# CCM_0020_transmitter.net
KiCad netlist of a schematic drawn in EAGLE
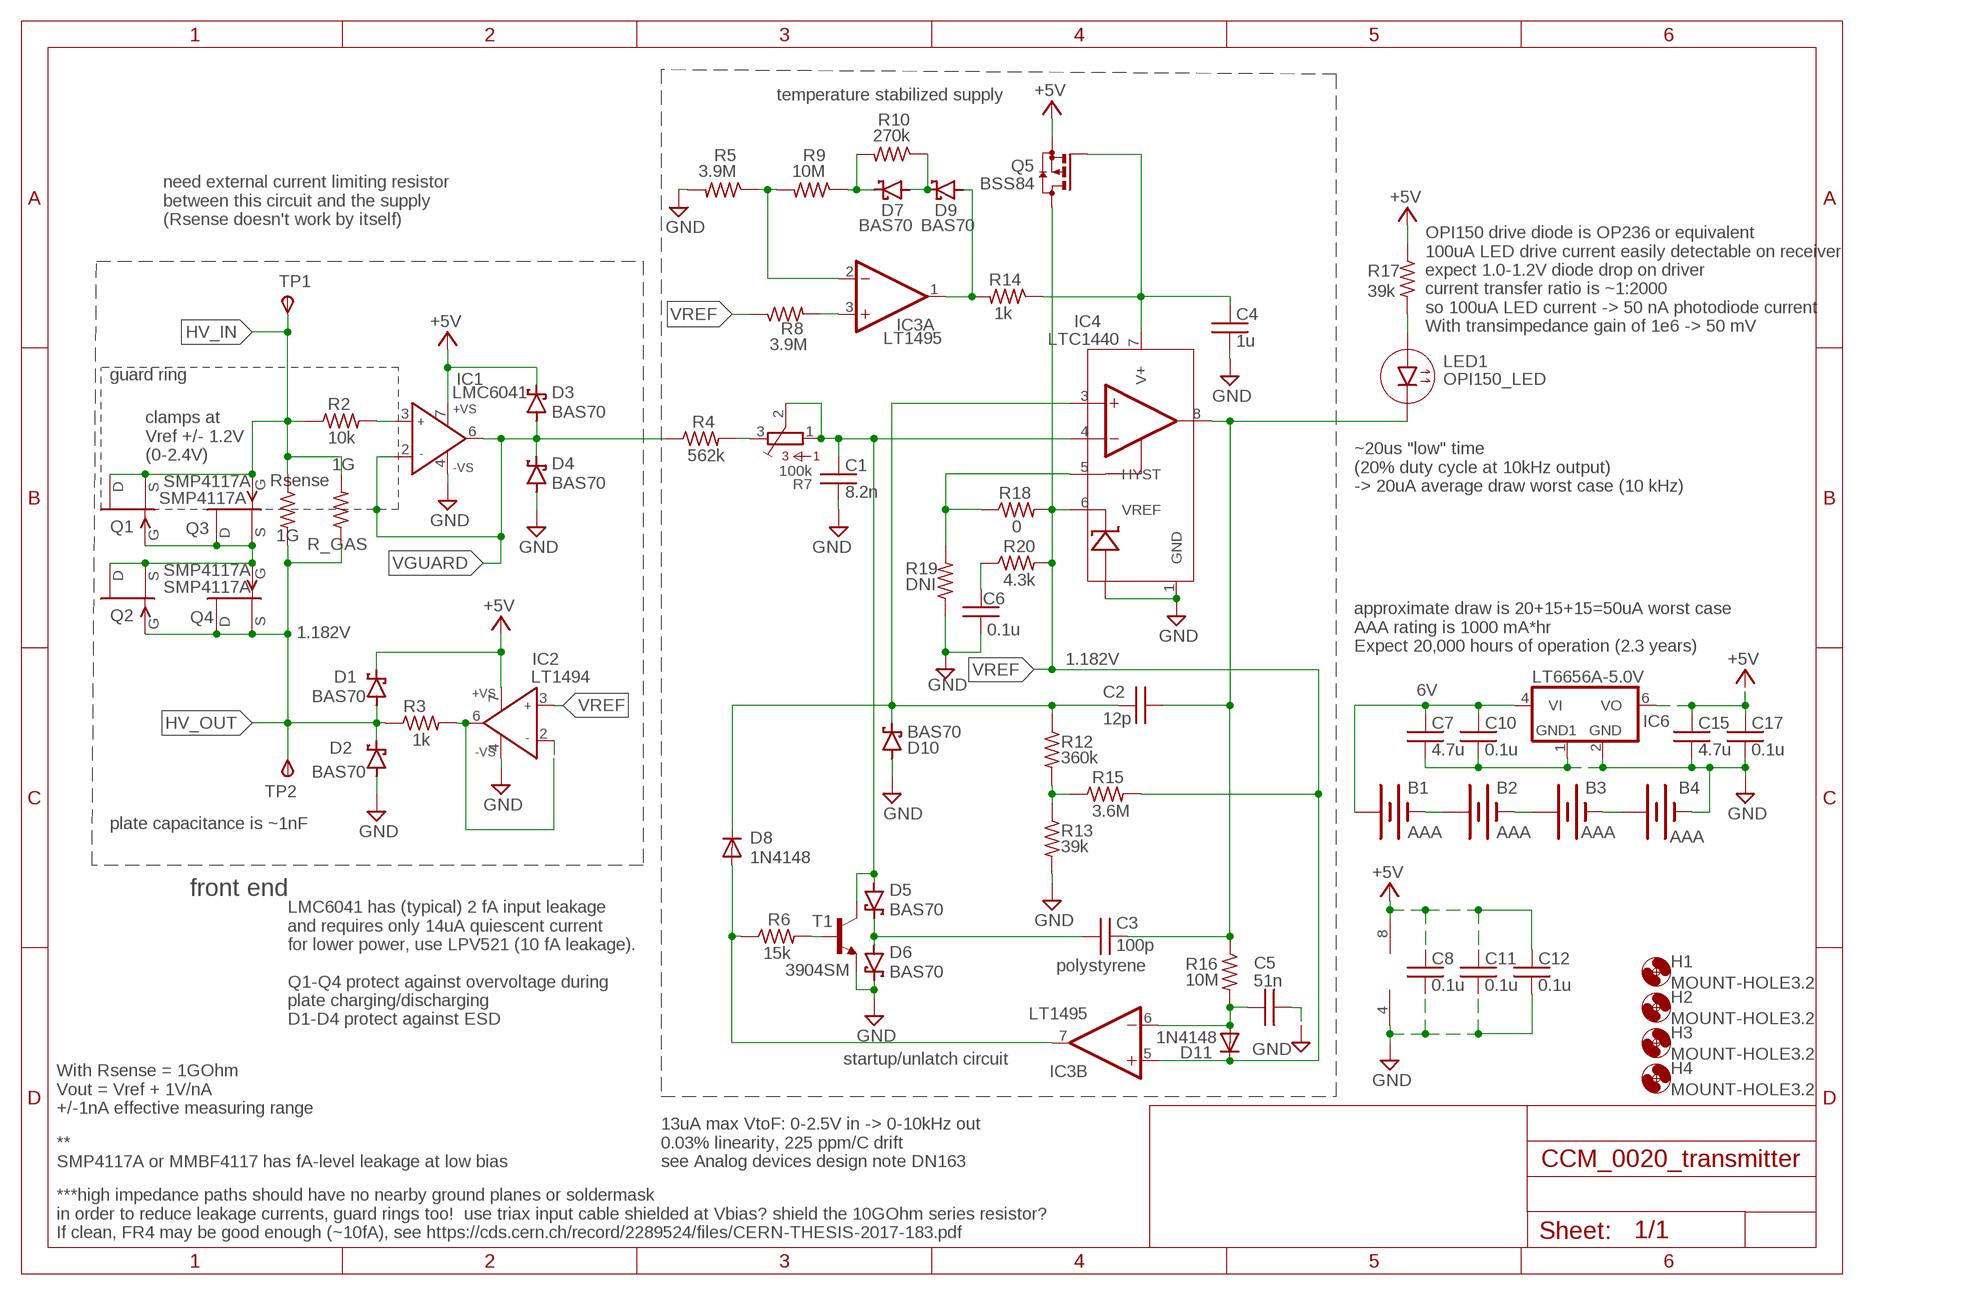
[diagram p0: schematic, sheet 1]

(export (version "E")
  (design (tool "Eeschema 10.0.6"))
  (components
    (comp (ref "B1")
      (value "AAA")
      (footprint "eagle-import:AAA_SM")
      (libsource (lib "eagle-import") (part "AAA"))
    )
    (comp (ref "B2")
      (value "AAA")
      (footprint "eagle-import:AAA_SM")
      (libsource (lib "eagle-import") (part "AAA"))
    )
    (comp (ref "B3")
      (value "AAA")
      (footprint "eagle-import:AAA_SM")
      (libsource (lib "eagle-import") (part "AAA"))
    )
    (comp (ref "B4")
      (value "AAA")
      (footprint "eagle-import:AAA_SM")
      (libsource (lib "eagle-import") (part "AAA"))
    )
    (comp (ref "C1")
      (value "8.2n")
      (footprint "eagle-import:0603")
      (libsource (lib "eagle-import") (part "C0603"))
    )
    (comp (ref "C2")
      (value "12p")
      (footprint "eagle-import:0603")
      (libsource (lib "eagle-import") (part "C0603"))
    )
    (comp (ref "C3")
      (value "100p")
      (footprint "eagle-import:0603")
      (libsource (lib "eagle-import") (part "C0603"))
    )
    (comp (ref "C4")
      (value "1u")
      (footprint "eagle-import:0603")
      (libsource (lib "eagle-import") (part "C0603"))
    )
    (comp (ref "C5")
      (value "51n")
      (footprint "eagle-import:0603")
      (libsource (lib "eagle-import") (part "C0603"))
    )
    (comp (ref "C6")
      (value "0.1u")
      (footprint "eagle-import:0603")
      (libsource (lib "eagle-import") (part "C0603"))
    )
    (comp (ref "C7")
      (value "4.7u")
      (footprint "eagle-import:0603")
      (libsource (lib "eagle-import") (part "C0603"))
    )
    (comp (ref "C8")
      (value "0.1u")
      (footprint "eagle-import:0603")
      (libsource (lib "eagle-import") (part "C0603"))
    )
    (comp (ref "C10")
      (value "0.1u")
      (footprint "eagle-import:0603")
      (libsource (lib "eagle-import") (part "C0603"))
    )
    (comp (ref "C11")
      (value "0.1u")
      (footprint "eagle-import:0603")
      (libsource (lib "eagle-import") (part "C0603"))
    )
    (comp (ref "C12")
      (value "0.1u")
      (footprint "eagle-import:0603")
      (libsource (lib "eagle-import") (part "C0603"))
    )
    (comp (ref "C15")
      (value "4.7u")
      (footprint "eagle-import:0603")
      (libsource (lib "eagle-import") (part "C0603"))
    )
    (comp (ref "C17")
      (value "0.1u")
      (footprint "eagle-import:0603")
      (libsource (lib "eagle-import") (part "C0603"))
    )
    (comp (ref "D1")
      (value "BAS70")
      (footprint "eagle-import:SOT23")
      (libsource (lib "eagle-import") (part "BAS70"))
    )
    (comp (ref "D2")
      (value "BAS70")
      (footprint "eagle-import:SOT23")
      (libsource (lib "eagle-import") (part "BAS70"))
    )
    (comp (ref "D3")
      (value "BAS70")
      (footprint "eagle-import:SOT23")
      (libsource (lib "eagle-import") (part "BAS70"))
    )
    (comp (ref "D4")
      (value "BAS70")
      (footprint "eagle-import:SOT23")
      (libsource (lib "eagle-import") (part "BAS70"))
    )
    (comp (ref "D5")
      (value "BAS70")
      (footprint "eagle-import:SOT23")
      (libsource (lib "eagle-import") (part "BAS70"))
    )
    (comp (ref "D6")
      (value "BAS70")
      (footprint "eagle-import:SOT23")
      (libsource (lib "eagle-import") (part "BAS70"))
    )
    (comp (ref "D7")
      (value "BAS70")
      (footprint "eagle-import:SOT23")
      (libsource (lib "eagle-import") (part "BAS70"))
    )
    (comp (ref "D8")
      (value "1N4148")
      (footprint "eagle-import:SOD323_ST")
      (libsource (lib "eagle-import") (part "1N4148"))
    )
    (comp (ref "D9")
      (value "BAS70")
      (footprint "eagle-import:SOT23")
      (libsource (lib "eagle-import") (part "BAS70"))
    )
    (comp (ref "D10")
      (value "BAS70")
      (footprint "eagle-import:SOT23")
      (libsource (lib "eagle-import") (part "BAS70"))
    )
    (comp (ref "D11")
      (value "1N4148")
      (footprint "eagle-import:SOD323_ST")
      (libsource (lib "eagle-import") (part "1N4148"))
    )
    (comp (ref "H1")
      (value "MOUNT-HOLE3.2")
      (footprint "eagle-import:3,2")
      (libsource (lib "eagle-import") (part "MOUNT-HOLE3.2"))
    )
    (comp (ref "H2")
      (value "MOUNT-HOLE3.2")
      (footprint "eagle-import:3,2")
      (libsource (lib "eagle-import") (part "MOUNT-HOLE3.2"))
    )
    (comp (ref "H3")
      (value "MOUNT-HOLE3.2")
      (footprint "eagle-import:3,2")
      (libsource (lib "eagle-import") (part "MOUNT-HOLE3.2"))
    )
    (comp (ref "H4")
      (value "MOUNT-HOLE3.2")
      (footprint "eagle-import:3,2")
      (libsource (lib "eagle-import") (part "MOUNT-HOLE3.2"))
    )
    (comp (ref "IC1")
      (value "LMC6041")
      (footprint "eagle-import:SO08")
      (libsource (lib "eagle-import") (part "AD825_A"))
    )
    (comp (ref "IC2")
      (value "LT1494")
      (footprint "eagle-import:SO08")
      (libsource (lib "eagle-import") (part "AD825_A"))
    )
    (comp (ref "IC3")
      (value "LT1495")
      (footprint "eagle-import:SO08")
      (libsource (lib "eagle-import") (part "LM393D"))
    )
    (comp (ref "IC4")
      (value "LTC1440")
      (footprint "eagle-import:SO8")
      (libsource (lib "eagle-import") (part "LTC1440"))
    )
    (comp (ref "IC6")
      (value "LT6656A-5.0V")
      (footprint "eagle-import:SOT23-6")
      (libsource (lib "eagle-import") (part "LT6656"))
    )
    (comp (ref "LED1")
      (value "OPI150_LED")
      (footprint "eagle-import:OPI150_LED")
      (libsource (lib "eagle-import") (part "OPI150_LED"))
    )
    (comp (ref "Q1")
      (value "SMP4117A")
      (footprint "eagle-import:SOT23")
      (libsource (lib "eagle-import") (part "?548SST4"))
    )
    (comp (ref "Q2")
      (value "SMP4117A")
      (footprint "eagle-import:SOT23")
      (libsource (lib "eagle-import") (part "?548SST4"))
    )
    (comp (ref "Q3")
      (value "SMP4117A")
      (footprint "eagle-import:SOT23")
      (libsource (lib "eagle-import") (part "?548SST4"))
    )
    (comp (ref "Q4")
      (value "SMP4117A")
      (footprint "eagle-import:SOT23")
      (libsource (lib "eagle-import") (part "?548SST4"))
    )
    (comp (ref "Q5")
      (value "BSS84")
      (footprint "eagle-import:SOT23")
      (libsource (lib "eagle-import") (part "BSS84"))
    )
    (comp (ref "R1")
      (value "1G")
      (footprint "eagle-import:2512")
      (libsource (lib "eagle-import") (part "RESISTOR2512"))
    )
    (comp (ref "R2")
      (value "10k")
      (footprint "eagle-import:0603")
      (libsource (lib "eagle-import") (part "R0603"))
    )
    (comp (ref "R3")
      (value "1k")
      (footprint "eagle-import:0603")
      (libsource (lib "eagle-import") (part "R0603"))
    )
    (comp (ref "R4")
      (value "562k")
      (footprint "eagle-import:0603")
      (libsource (lib "eagle-import") (part "R0603"))
    )
    (comp (ref "R5")
      (value "3.9M")
      (footprint "eagle-import:0603")
      (libsource (lib "eagle-import") (part "R0603"))
    )
    (comp (ref "R6")
      (value "15k")
      (footprint "eagle-import:0603")
      (libsource (lib "eagle-import") (part "R0603"))
    )
    (comp (ref "R7")
      (value "100k")
      (footprint "eagle-import:3386C")
      (libsource (lib "eagle-import") (part "3386-C"))
    )
    (comp (ref "R8")
      (value "3.9M")
      (footprint "eagle-import:0603")
      (libsource (lib "eagle-import") (part "R0603"))
    )
    (comp (ref "R9")
      (value "10M")
      (footprint "eagle-import:0603")
      (libsource (lib "eagle-import") (part "R0603"))
    )
    (comp (ref "R10")
      (value "270k")
      (footprint "eagle-import:0603")
      (libsource (lib "eagle-import") (part "R0603"))
    )
    (comp (ref "R12")
      (value "360k")
      (footprint "eagle-import:0603")
      (libsource (lib "eagle-import") (part "R0603"))
    )
    (comp (ref "R13")
      (value "39k")
      (footprint "eagle-import:0603")
      (libsource (lib "eagle-import") (part "R0603"))
    )
    (comp (ref "R14")
      (value "1k")
      (footprint "eagle-import:0603")
      (libsource (lib "eagle-import") (part "R0603"))
    )
    (comp (ref "R15")
      (value "3.6M")
      (footprint "eagle-import:0603")
      (libsource (lib "eagle-import") (part "R0603"))
    )
    (comp (ref "R16")
      (value "10M")
      (footprint "eagle-import:0603")
      (libsource (lib "eagle-import") (part "R0603"))
    )
    (comp (ref "R17")
      (value "39k")
      (footprint "eagle-import:0603")
      (libsource (lib "eagle-import") (part "R0603"))
    )
    (comp (ref "R18")
      (value "0")
      (footprint "eagle-import:0603")
      (libsource (lib "eagle-import") (part "R0603"))
    )
    (comp (ref "R19")
      (value "DNI")
      (footprint "eagle-import:0603")
      (libsource (lib "eagle-import") (part "R0603"))
    )
    (comp (ref "R20")
      (value "4.3k")
      (footprint "eagle-import:0603")
      (libsource (lib "eagle-import") (part "R0603"))
    )
    (comp (ref "R_GAS")
      (value "1G")
      (footprint "eagle-import:0309_10")
      (libsource (lib "eagle-import") (part "R-US_0309/10"))
    )
    (comp (ref "T1")
      (value "3904SM")
      (footprint "eagle-import:SOT23")
      (libsource (lib "eagle-import") (part "3904SM"))
    )
    (comp (ref "TP1")
      (value "TPSPAD1-17")
      (footprint "eagle-import:P1-17")
      (libsource (lib "eagle-import") (part "TPSPAD1-17"))
    )
    (comp (ref "TP2")
      (value "TPSPAD1-17")
      (footprint "eagle-import:P1-17")
      (libsource (lib "eagle-import") (part "TPSPAD1-17"))
    )
  )
  (nets
    (net (code "1") (name "+5V") (class "Default")
      (node (ref "C11") (pin "1") (pinfunction "1_1") (pintype "passive"))
      (node (ref "C12") (pin "1") (pinfunction "1_1") (pintype "passive"))
      (node (ref "C15") (pin "1") (pinfunction "1_1") (pintype "passive"))
      (node (ref "C17") (pin "1") (pinfunction "1_1") (pintype "passive"))
      (node (ref "C8") (pin "1") (pinfunction "1_1") (pintype "passive"))
      (node (ref "D1") (pin "3") (pinfunction "C_3") (pintype "passive"))
      (node (ref "D3") (pin "3") (pinfunction "C_3") (pintype "passive"))
      (node (ref "IC1") (pin "7") (pinfunction "+VS_7") (pintype "input"))
      (node (ref "IC2") (pin "7") (pinfunction "+VS_7") (pintype "input"))
      (node (ref "IC3") (pin "8") (pinfunction "V+_8") (pintype "power_in"))
      (node (ref "IC6") (pin "6") (pinfunction "VO_6") (pintype "passive"))
      (node (ref "Q5") (pin "2") (pinfunction "S_2") (pintype "passive"))
      (node (ref "R17") (pin "1") (pinfunction "1_1") (pintype "passive"))
    )
    (net (code "2") (name "GND") (class "Default")
      (node (ref "B4") (pin "-") (pinfunction "-_-") (pintype "power_in"))
      (node (ref "C1") (pin "2") (pinfunction "2_2") (pintype "passive"))
      (node (ref "C10") (pin "2") (pinfunction "2_2") (pintype "passive"))
      (node (ref "C11") (pin "2") (pinfunction "2_2") (pintype "passive"))
      (node (ref "C12") (pin "2") (pinfunction "2_2") (pintype "passive"))
      (node (ref "C15") (pin "2") (pinfunction "2_2") (pintype "passive"))
      (node (ref "C17") (pin "2") (pinfunction "2_2") (pintype "passive"))
      (node (ref "C4") (pin "2") (pinfunction "2_2") (pintype "passive"))
      (node (ref "C5") (pin "2") (pinfunction "2_2") (pintype "passive"))
      (node (ref "C6") (pin "1") (pinfunction "1_1") (pintype "passive"))
      (node (ref "C7") (pin "2") (pinfunction "2_2") (pintype "passive"))
      (node (ref "C8") (pin "2") (pinfunction "2_2") (pintype "passive"))
      (node (ref "D10") (pin "1") (pinfunction "A_1") (pintype "passive"))
      (node (ref "D2") (pin "1") (pinfunction "A_1") (pintype "passive"))
      (node (ref "D4") (pin "1") (pinfunction "A_1") (pintype "passive"))
      (node (ref "D6") (pin "3") (pinfunction "C_3") (pintype "passive"))
      (node (ref "IC1") (pin "4") (pinfunction "-VS_4") (pintype "input"))
      (node (ref "IC2") (pin "4") (pinfunction "-VS_4") (pintype "input"))
      (node (ref "IC3") (pin "4") (pinfunction "V-_4") (pintype "power_in"))
      (node (ref "IC4") (pin "1") (pinfunction "GND_1") (pintype "power_in"))
      (node (ref "IC4") (pin "2") (pinfunction "V-_2") (pintype "passive"))
      (node (ref "IC6") (pin "1") (pinfunction "GND1_1") (pintype "passive"))
      (node (ref "IC6") (pin "2") (pinfunction "GND_2") (pintype "passive"))
      (node (ref "R13") (pin "2") (pinfunction "2_2") (pintype "passive"))
      (node (ref "R19") (pin "1") (pinfunction "1_1") (pintype "passive"))
      (node (ref "R5") (pin "2") (pinfunction "2_2") (pintype "passive"))
      (node (ref "T1") (pin "2") (pinfunction "E_2") (pintype "passive"))
    )
    (net (code "3") (name "HV_IN") (class "Default")
      (node (ref "Q1") (pin "1") (pinfunction "D_1") (pintype "passive"))
      (node (ref "Q1") (pin "2") (pinfunction "S_2") (pintype "passive"))
      (node (ref "Q3") (pin "3") (pinfunction "G_3") (pintype "passive"))
      (node (ref "R1") (pin "1") (pinfunction "1_1") (pintype "passive"))
      (node (ref "R2") (pin "1") (pinfunction "1_1") (pintype "passive"))
      (node (ref "R_GAS") (pin "2") (pinfunction "2_2") (pintype "passive"))
      (node (ref "TP1") (pin "TP") (pinfunction "PP_TP") (pintype "input"))
    )
    (net (code "4") (name "HV_OUT") (class "Default")
      (node (ref "D1") (pin "1") (pinfunction "A_1") (pintype "passive"))
      (node (ref "D2") (pin "3") (pinfunction "C_3") (pintype "passive"))
      (node (ref "Q2") (pin "3") (pinfunction "G_3") (pintype "passive"))
      (node (ref "Q4") (pin "1") (pinfunction "D_1") (pintype "passive"))
      (node (ref "Q4") (pin "2") (pinfunction "S_2") (pintype "passive"))
      (node (ref "R1") (pin "2") (pinfunction "2_2") (pintype "passive"))
      (node (ref "R3") (pin "1") (pinfunction "1_1") (pintype "passive"))
      (node (ref "R_GAS") (pin "1") (pinfunction "1_1") (pintype "passive"))
      (node (ref "TP2") (pin "TP") (pinfunction "PP_TP") (pintype "input"))
    )
    (net (code "5") (name "Net-(B1-Pad-)") (class "Default")
      (node (ref "B1") (pin "-") (pinfunction "-_-") (pintype "power_in"))
      (node (ref "B2") (pin "+") (pinfunction "+_+") (pintype "power_in"))
    )
    (net (code "6") (name "Net-(B2-Pad-)") (class "Default")
      (node (ref "B2") (pin "-") (pinfunction "-_-") (pintype "power_in"))
      (node (ref "B3") (pin "+") (pinfunction "+_+") (pintype "power_in"))
    )
    (net (code "7") (name "Net-(B3-Pad-)") (class "Default")
      (node (ref "B3") (pin "-") (pinfunction "-_-") (pintype "power_in"))
      (node (ref "B4") (pin "+") (pinfunction "+_+") (pintype "power_in"))
    )
    (net (code "8") (name "Net-(C6-Pad2)") (class "Default")
      (node (ref "C6") (pin "2") (pinfunction "2_2") (pintype "passive"))
      (node (ref "R20") (pin "1") (pinfunction "1_1") (pintype "passive"))
    )
    (net (code "9") (name "Net-(D5-A)") (class "Default")
      (node (ref "C1") (pin "1") (pinfunction "1_1") (pintype "passive"))
      (node (ref "D5") (pin "1") (pinfunction "A_1") (pintype "passive"))
      (node (ref "IC4") (pin "4") (pinfunction "-IN_4") (pintype "input"))
      (node (ref "R7") (pin "1") (pinfunction "1_1") (pintype "passive"))
      (node (ref "R7") (pin "2") (pinfunction "2_2") (pintype "passive"))
      (node (ref "T1") (pin "3") (pinfunction "C_3") (pintype "passive"))
    )
    (net (code "10") (name "Net-(D5-C)") (class "Default")
      (node (ref "C3") (pin "1") (pinfunction "1_1") (pintype "passive"))
      (node (ref "D5") (pin "3") (pinfunction "C_3") (pintype "passive"))
      (node (ref "D6") (pin "1") (pinfunction "A_1") (pintype "passive"))
    )
    (net (code "11") (name "Net-(D7-A)") (class "Default")
      (node (ref "D7") (pin "1") (pinfunction "A_1") (pintype "passive"))
      (node (ref "D9") (pin "3") (pinfunction "C_3") (pintype "passive"))
      (node (ref "R10") (pin "1") (pinfunction "1_1") (pintype "passive"))
    )
    (net (code "12") (name "Net-(D7-C)") (class "Default")
      (node (ref "D7") (pin "3") (pinfunction "C_3") (pintype "passive"))
      (node (ref "R10") (pin "2") (pinfunction "2_2") (pintype "passive"))
      (node (ref "R9") (pin "1") (pinfunction "1_1") (pintype "passive"))
    )
    (net (code "13") (name "Net-(D9-A)") (class "Default")
      (node (ref "D9") (pin "1") (pinfunction "A_1") (pintype "passive"))
      (node (ref "IC3") (pin "1") (pinfunction "OUT_1") (pintype "output"))
      (node (ref "R14") (pin "2") (pinfunction "2_2") (pintype "passive"))
    )
    (net (code "14") (name "Net-(D10-C)") (class "Default")
      (node (ref "C2") (pin "1") (pinfunction "1_1") (pintype "passive"))
      (node (ref "D10") (pin "3") (pinfunction "C_3") (pintype "passive"))
      (node (ref "D8") (pin "C") (pinfunction "C_C") (pintype "passive"))
      (node (ref "IC4") (pin "3") (pinfunction "+IN_3") (pintype "input"))
      (node (ref "R12") (pin "1") (pinfunction "1_1") (pintype "passive"))
    )
    (net (code "15") (name "Net-(IC1-IN+)") (class "Default")
      (node (ref "IC1") (pin "3") (pinfunction "IN+_3") (pintype "input"))
      (node (ref "R2") (pin "2") (pinfunction "2_2") (pintype "passive"))
    )
    (net (code "16") (name "Net-(IC2-IN-)") (class "Default")
      (node (ref "IC2") (pin "2") (pinfunction "IN-_2") (pintype "input"))
      (node (ref "IC2") (pin "6") (pinfunction "OUT_6") (pintype "output"))
      (node (ref "R3") (pin "2") (pinfunction "2_2") (pintype "passive"))
    )
    (net (code "17") (name "Net-(IC3A-+IN)") (class "Default")
      (node (ref "IC3") (pin "3") (pinfunction "+IN_3") (pintype "input"))
      (node (ref "R8") (pin "2") (pinfunction "2_2") (pintype "passive"))
    )
    (net (code "18") (name "Net-(IC3A--IN)") (class "Default")
      (node (ref "IC3") (pin "2") (pinfunction "-IN_2") (pintype "input"))
      (node (ref "R5") (pin "1") (pinfunction "1_1") (pintype "passive"))
      (node (ref "R9") (pin "2") (pinfunction "2_2") (pintype "passive"))
    )
    (net (code "19") (name "Net-(IC3B--IN)") (class "Default")
      (node (ref "C5") (pin "1") (pinfunction "1_1") (pintype "passive"))
      (node (ref "D11") (pin "A") (pinfunction "A_A") (pintype "passive"))
      (node (ref "IC3") (pin "6") (pinfunction "-IN_6") (pintype "input"))
      (node (ref "R16") (pin "2") (pinfunction "2_2") (pintype "passive"))
    )
    (net (code "20") (name "Net-(IC3B-OUT)") (class "Default")
      (node (ref "D8") (pin "A") (pinfunction "A_A") (pintype "passive"))
      (node (ref "IC3") (pin "7") (pinfunction "OUT_7") (pintype "output"))
      (node (ref "R6") (pin "1") (pinfunction "1_1") (pintype "passive"))
    )
    (net (code "21") (name "Net-(IC4-HYST)") (class "Default")
      (node (ref "IC4") (pin "5") (pinfunction "HYST_5") (pintype "input"))
      (node (ref "R18") (pin "1") (pinfunction "1_1") (pintype "passive"))
      (node (ref "R19") (pin "2") (pinfunction "2_2") (pintype "passive"))
    )
    (net (code "22") (name "Net-(IC4-OUT)") (class "Default")
      (node (ref "C2") (pin "2") (pinfunction "2_2") (pintype "passive"))
      (node (ref "C3") (pin "2") (pinfunction "2_2") (pintype "passive"))
      (node (ref "IC4") (pin "8") (pinfunction "OUT_8") (pintype "output"))
      (node (ref "LED1") (pin "P$2") (pinfunction "2(C)_P$2") (pintype "passive"))
      (node (ref "R16") (pin "1") (pinfunction "1_1") (pintype "passive"))
    )
    (net (code "23") (name "Net-(IC4-V+)") (class "Default")
      (node (ref "C4") (pin "1") (pinfunction "1_1") (pintype "passive"))
      (node (ref "IC4") (pin "7") (pinfunction "V+_7") (pintype "power_in"))
      (node (ref "Q5") (pin "1") (pinfunction "G_1") (pintype "passive"))
      (node (ref "R14") (pin "1") (pinfunction "1_1") (pintype "passive"))
    )
    (net (code "24") (name "Net-(IC6-VI)") (class "Default")
      (node (ref "B1") (pin "+") (pinfunction "+_+") (pintype "power_in"))
      (node (ref "C10") (pin "1") (pinfunction "1_1") (pintype "passive"))
      (node (ref "C7") (pin "1") (pinfunction "1_1") (pintype "passive"))
      (node (ref "IC6") (pin "4") (pinfunction "VI_4") (pintype "input"))
    )
    (net (code "25") (name "Net-(LED1-1(A))") (class "Default")
      (node (ref "LED1") (pin "P$1") (pinfunction "1(A)_P$1") (pintype "passive"))
      (node (ref "R17") (pin "2") (pinfunction "2_2") (pintype "passive"))
    )
    (net (code "26") (name "Net-(Q1-G)") (class "Default")
      (node (ref "Q1") (pin "3") (pinfunction "G_3") (pintype "passive"))
      (node (ref "Q2") (pin "1") (pinfunction "D_1") (pintype "passive"))
      (node (ref "Q2") (pin "2") (pinfunction "S_2") (pintype "passive"))
      (node (ref "Q3") (pin "1") (pinfunction "D_1") (pintype "passive"))
      (node (ref "Q3") (pin "2") (pinfunction "S_2") (pintype "passive"))
      (node (ref "Q4") (pin "3") (pinfunction "G_3") (pintype "passive"))
    )
    (net (code "27") (name "Net-(R4-Pad2)") (class "Default")
      (node (ref "R4") (pin "2") (pinfunction "2_2") (pintype "passive"))
      (node (ref "R7") (pin "3") (pinfunction "3_3") (pintype "passive"))
    )
    (net (code "28") (name "Net-(R12-Pad2)") (class "Default")
      (node (ref "R12") (pin "2") (pinfunction "2_2") (pintype "passive"))
      (node (ref "R13") (pin "1") (pinfunction "1_1") (pintype "passive"))
      (node (ref "R15") (pin "1") (pinfunction "1_1") (pintype "passive"))
    )
    (net (code "29") (name "Net-(T1-B)") (class "Default")
      (node (ref "R6") (pin "2") (pinfunction "2_2") (pintype "passive"))
      (node (ref "T1") (pin "1") (pinfunction "B_1") (pintype "passive"))
    )
    (net (code "30") (name "VGUARD") (class "Default")
      (node (ref "D3") (pin "1") (pinfunction "A_1") (pintype "passive"))
      (node (ref "D4") (pin "3") (pinfunction "C_3") (pintype "passive"))
      (node (ref "IC1") (pin "2") (pinfunction "IN-_2") (pintype "input"))
      (node (ref "IC1") (pin "6") (pinfunction "OUT_6") (pintype "output"))
      (node (ref "R4") (pin "1") (pinfunction "1_1") (pintype "passive"))
    )
    (net (code "31") (name "VREF") (class "Default")
      (node (ref "D11") (pin "C") (pinfunction "C_C") (pintype "passive"))
      (node (ref "IC2") (pin "3") (pinfunction "IN+_3") (pintype "input"))
      (node (ref "IC3") (pin "5") (pinfunction "+IN_5") (pintype "input"))
      (node (ref "IC4") (pin "6") (pinfunction "VREF_6") (pintype "passive"))
      (node (ref "Q5") (pin "3") (pinfunction "D_3") (pintype "passive"))
      (node (ref "R15") (pin "2") (pinfunction "2_2") (pintype "passive"))
      (node (ref "R18") (pin "2") (pinfunction "2_2") (pintype "passive"))
      (node (ref "R20") (pin "2") (pinfunction "2_2") (pintype "passive"))
      (node (ref "R8") (pin "1") (pinfunction "1_1") (pintype "passive"))
    )
  )
)
